# Test_Gate.net
KiCad netlist of a schematic drawn in Altium Designer
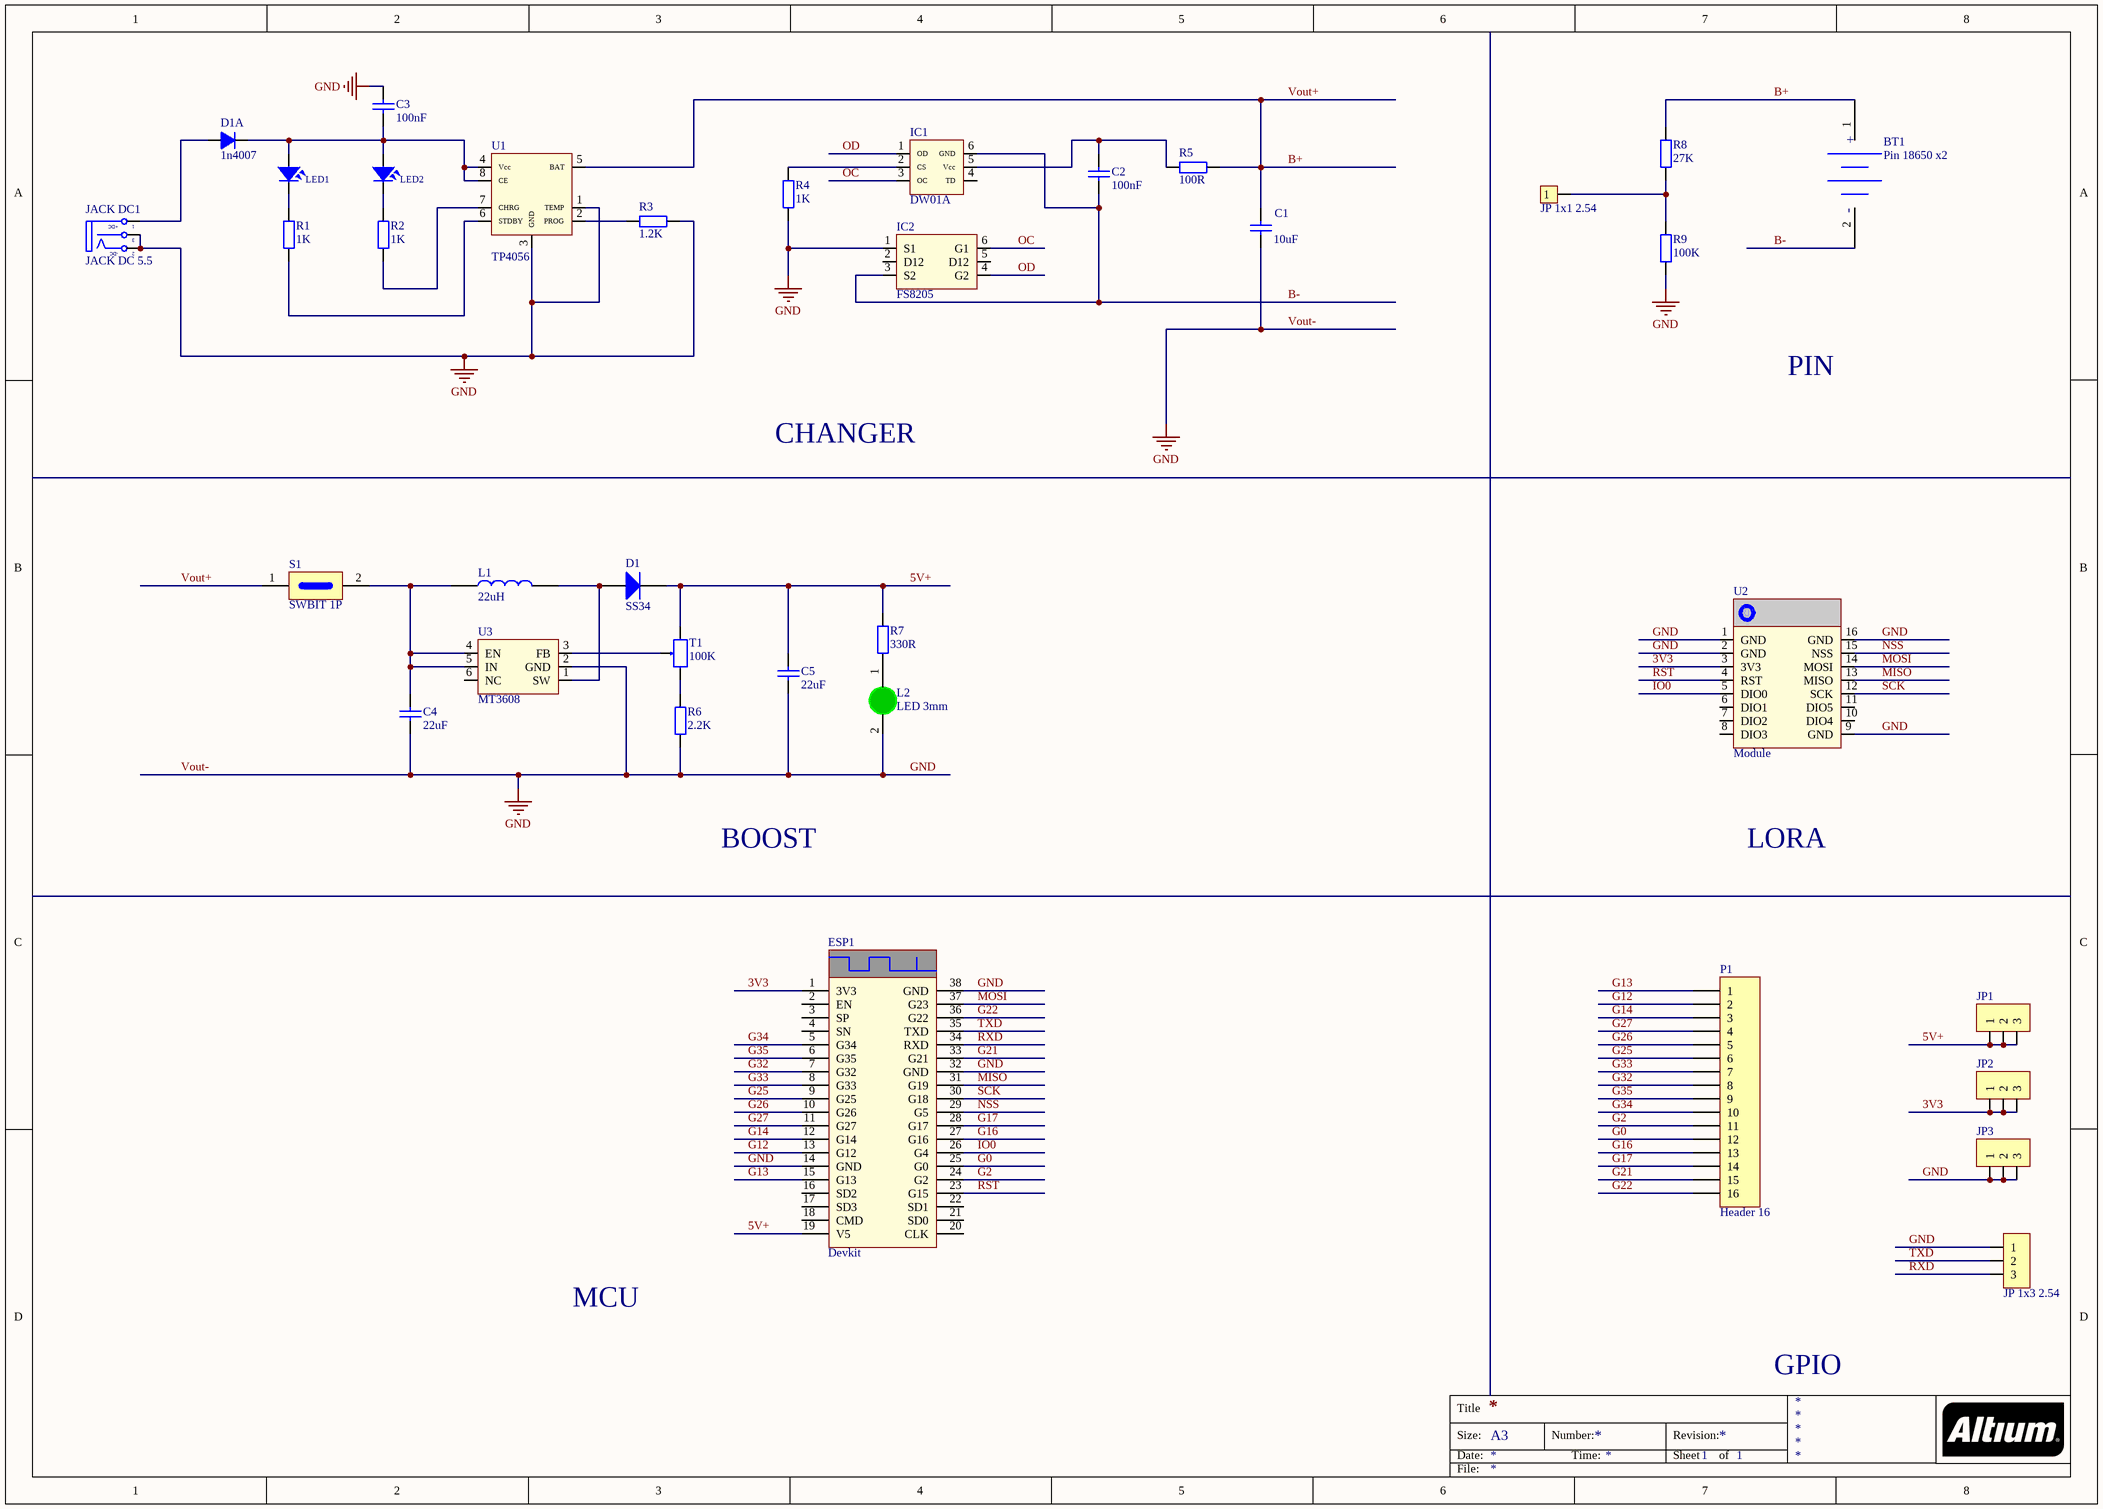
[diagram p0: Test Gate.SchDoc]

(export (version "E")
  (design (tool "Eeschema 10.0.6"))
  (components
    (comp (ref "BT1")
      (value "Pin 18650 x2")
      (footprint "De Pin 18650 x2")
      (libsource (lib "Lib_byDuy") (part "De Pin 18650 x2"))
    )
    (comp (ref "C1")
      (value "10uF")
      (footprint "tu 0805")
      (description "Dán")
      (libsource (lib "Altium_Lib_by_KhueNguyenCreator") (part "Tu 0805 104 50V 10%"))
    )
    (comp (ref "C2")
      (value "100nF")
      (footprint "tu 0805")
      (description "Dán")
      (libsource (lib "Altium_Lib_by_KhueNguyenCreator") (part "Tu 0805 104 50V 10%"))
    )
    (comp (ref "C3")
      (value "100nF")
      (footprint "tu 0805")
      (description "Dán")
      (libsource (lib "Altium_Lib_by_KhueNguyenCreator") (part "Tu 0805 104 50V 10%"))
    )
    (comp (ref "C4")
      (value "22uF")
      (footprint "tu 1206")
      (description "Dán")
      (libsource (lib "Altium_Lib_by_KhueNguyenCreator") (part "Tu 1206 226 16V 20%"))
    )
    (comp (ref "C5")
      (value "22uF")
      (footprint "tu 1206")
      (description "Dán")
      (libsource (lib "Altium_Lib_by_KhueNguyenCreator") (part "Tu 1206 226 16V 20%"))
    )
    (comp (ref "D1")
      (value "SS34")
      (footprint "DIODE SMA")
      (description "Dán")
      (libsource (lib "Altium_Lib_by_KhueNguyenCreator") (part "Diode SS34 ( 1N5822 )"))
    )
    (comp (ref "D1A")
      (value "1n4007")
      (footprint "DIODE 1A")
      (description "Cắm")
      (libsource (lib "Altium_Lib_by_KhueNguyenCreator") (part "Diode 1N4007"))
    )
    (comp (ref "ESP1")
      (value "Devkit")
      (footprint "ESP32 DEVKIT 38Pin")
      (description "Board")
      (libsource (lib "Lib_byDuy") (part "ESP32 DEV KIT"))
    )
    (comp (ref "IC1") (value "DW01A") (footprint "DW01A") (libsource (lib "Lib_byDuy") (part "DW01A")))
    (comp (ref "IC2")
      (value "FS8205")
      (footprint "FS8205")
      (description "SOT23-6")
      (libsource (lib "Lib_byDuy") (part "FS8205"))
    )
    (comp (ref "JACK DC1")
      (value "JACK DC 5.5")
      (footprint "JACK DC 5.5")
      (libsource (lib "Altium_Lib_by_KhueNguyenCreator") (part "JACK DC 5.5"))
    )
    (comp (ref "JP1")
      (value "JP 1x3 2.54")
      (footprint "JP 1x3 CT")
      (description "Cắm")
      (libsource (lib "Altium_Lib_by_KhueNguyenCreator") (part "JP 1x3 2.54 Cai Thang"))
    )
    (comp (ref "JP2")
      (value "JP 1x3 2.54")
      (footprint "JP 1x3 CT")
      (description "Cắm")
      (libsource (lib "Altium_Lib_by_KhueNguyenCreator") (part "JP 1x3 2.54 Cai Thang"))
    )
    (comp (ref "JP3")
      (value "JP 1x3 2.54")
      (footprint "JP 1x3 CT")
      (description "Cắm")
      (libsource (lib "Altium_Lib_by_KhueNguyenCreator") (part "JP 1x3 2.54 Cai Thang"))
    )
    (comp (ref "JP4")
      (value "JP 1x1 2.54")
      (footprint "JP 1x1 DT")
      (description "Cắm")
      (libsource (lib "Altium_Lib_by_KhueNguyenCreator") (part "JP 1x1 2.54 Duc Thang"))
    )
    (comp (ref "JP5")
      (value "JP 1x3 2.54")
      (footprint "JP 1x3 CT")
      (description "Cắm")
      (libsource (lib "") (part "JP 1x3 2.54 Cai Thang_1"))
    )
    (comp (ref "L1")
      (value "22uH")
      (footprint "Cuon Cam 7x7x5")
      (description "Dán")
      (libsource (lib "Altium_Lib_by_KhueNguyenCreator") (part "CUON CAM 47uH SMD"))
    )
    (comp (ref "L2")
      (value "LED 3mm")
      (footprint "LED-3MM-GREEN")
      (description "Cắm")
      (libsource (lib "Altium_Lib_by_KhueNguyenCreator") (part "LED 3mm Xanh La"))
    )
    (comp (ref "LED1")
      (value "LED SMD")
      (footprint "SM-LED-0805-Red")
      (libsource (lib "My library altium") (part "LED SMD 0805"))
    )
    (comp (ref "LED2")
      (value "LED SMD")
      (footprint "SM-LED-0805-Red")
      (libsource (lib "My library altium") (part "LED SMD 0805"))
    )
    (comp (ref "P1")
      (value "Header 16")
      (footprint "HDR1X16")
      (description "Header, 16-Pin")
      (fields (field (name "PUBLISHER") "Altium Limited"))
      (libsource (lib "My library altium") (part "Header 16"))
    )
    (comp (ref "R1")
      (value "1K")
      (footprint "tro smd 0805")
      (description "Dán")
      (libsource (lib "Altium_Lib_by_KhueNguyenCreator") (part "Tro 0805 5% 1k"))
    )
    (comp (ref "R2")
      (value "1K")
      (footprint "tro smd 0805")
      (description "Dán")
      (libsource (lib "Altium_Lib_by_KhueNguyenCreator") (part "Tro 0805 5% 1k"))
    )
    (comp (ref "R3")
      (value "1.2K")
      (footprint "tro smd 0805")
      (description "Dán")
      (libsource (lib "Altium_Lib_by_KhueNguyenCreator") (part "Tro 0805 5% 1k"))
    )
    (comp (ref "R4")
      (value "1K")
      (footprint "tro smd 0805")
      (description "Dán")
      (libsource (lib "Altium_Lib_by_KhueNguyenCreator") (part "Tro 0805 5% 1k"))
    )
    (comp (ref "R5")
      (value "100R")
      (footprint "tro smd 0805")
      (description "Dán")
      (libsource (lib "Altium_Lib_by_KhueNguyenCreator") (part "Tro 0805 5% 1k"))
    )
    (comp (ref "R6")
      (value "2.2K")
      (footprint "tro smd 0805")
      (description "Dán")
      (libsource (lib "Altium_Lib_by_KhueNguyenCreator") (part "Tro 0805 5% 1k"))
    )
    (comp (ref "R7")
      (value "330R")
      (footprint "tro smd 0805")
      (description "Dán")
      (libsource (lib "Altium_Lib_by_KhueNguyenCreator") (part "Tro 0805 5% 1k"))
    )
    (comp (ref "R8")
      (value "27K")
      (footprint "tro smd 0805")
      (description "Dán")
      (libsource (lib "Altium_Lib_by_KhueNguyenCreator") (part "Tro 0805 5% 1k"))
    )
    (comp (ref "R9")
      (value "100K")
      (footprint "tro smd 0805")
      (description "Dán")
      (libsource (lib "Altium_Lib_by_KhueNguyenCreator") (part "Tro 0805 5% 1k"))
    )
    (comp (ref "S1")
      (value "SWBIT 1P")
      (footprint "SWBIT 1P DIP")
      (libsource (lib "ThinhNguyenLib") (part "SWBIT 1P"))
    )
    (comp (ref "T1")
      (value "100K")
      (footprint "Bien Tro Vi Chinh Dung")
      (description "Cắm")
      (libsource (lib "Altium_Lib_by_KhueNguyenCreator") (part "Bien Tro Tinh Chinh 10K Dung"))
    )
    (comp (ref "U1") (value "TP4056") (footprint "TP4056") (libsource (lib "Lib_byDuy") (part "TP4056")))
    (comp (ref "U2")
      (value "Module")
      (footprint "LoRa Ra 02 Module 2")
      (libsource (lib "Lib_byDuy") (part "LoRa Ra 02 Module 2"))
    )
    (comp (ref "U3")
      (value "MT3608")
      (footprint "MT3608")
      (description "SMD")
      (libsource (lib "Lib_byDuy") (part "MT3608"))
    )
  )
  (nets
    (net (code "1") (name "/3V3") (class "Default")
      (node (ref "ESP1") (pin "1") (pinfunction "3V3_1") (pintype "passive"))
      (node (ref "JP2") (pin "1") (pinfunction "1_1") (pintype "passive"))
      (node (ref "JP2") (pin "2") (pinfunction "2_2") (pintype "passive"))
      (node (ref "JP2") (pin "3") (pinfunction "3_3") (pintype "passive"))
      (node (ref "U2") (pin "3") (pinfunction "3V3_3") (pintype "passive"))
    )
    (net (code "2") (name "/5V+") (class "Default")
      (node (ref "C5") (pin "1") (pinfunction "1_1") (pintype "passive"))
      (node (ref "D1") (pin "2") (pinfunction "K_2") (pintype "passive"))
      (node (ref "ESP1") (pin "19") (pinfunction "V5_19") (pintype "passive"))
      (node (ref "JP1") (pin "1") (pinfunction "1_1") (pintype "passive"))
      (node (ref "JP1") (pin "2") (pinfunction "2_2") (pintype "passive"))
      (node (ref "JP1") (pin "3") (pinfunction "3_3") (pintype "passive"))
      (node (ref "R7") (pin "1") (pinfunction "1_1") (pintype "passive"))
      (node (ref "T1") (pin "3") (pinfunction "3_3") (pintype "passive"))
    )
    (net (code "3") (name "/B+") (class "Default")
      (node (ref "BT1") (pin "1") (pinfunction "+_1") (pintype "passive"))
      (node (ref "C1") (pin "1") (pinfunction "1_1") (pintype "passive"))
      (node (ref "R5") (pin "2") (pinfunction "2_2") (pintype "passive"))
      (node (ref "R8") (pin "1") (pinfunction "1_1") (pintype "passive"))
      (node (ref "S1") (pin "1") (pinfunction "1_1") (pintype "passive"))
      (node (ref "U1") (pin "5") (pinfunction "BAT_5") (pintype "passive"))
    )
    (net (code "4") (name "/B-") (class "Default")
      (node (ref "BT1") (pin "2") (pinfunction "-_2") (pintype "passive"))
      (node (ref "C2") (pin "2") (pinfunction "2_2") (pintype "passive"))
      (node (ref "IC1") (pin "6") (pinfunction "GND_6") (pintype "passive"))
      (node (ref "IC2") (pin "3") (pinfunction "S2_3") (pintype "passive"))
    )
    (net (code "5") (name "/G0") (class "Default")
      (node (ref "ESP1") (pin "25") (pinfunction "G0_25") (pintype "passive"))
      (node (ref "P1") (pin "12") (pinfunction "12_12") (pintype "passive"))
    )
    (net (code "6") (name "/G2") (class "Default")
      (node (ref "ESP1") (pin "24") (pinfunction "G2_24") (pintype "passive"))
      (node (ref "P1") (pin "11") (pinfunction "11_11") (pintype "passive"))
    )
    (net (code "7") (name "/G12") (class "Default")
      (node (ref "ESP1") (pin "13") (pinfunction "G12_13") (pintype "passive"))
      (node (ref "P1") (pin "2") (pinfunction "2_2") (pintype "passive"))
    )
    (net (code "8") (name "/G13") (class "Default")
      (node (ref "ESP1") (pin "15") (pinfunction "G13_15") (pintype "passive"))
      (node (ref "P1") (pin "1") (pinfunction "1_1") (pintype "passive"))
    )
    (net (code "9") (name "/G14") (class "Default")
      (node (ref "ESP1") (pin "12") (pinfunction "G14_12") (pintype "passive"))
      (node (ref "P1") (pin "3") (pinfunction "3_3") (pintype "passive"))
    )
    (net (code "10") (name "/G16") (class "Default")
      (node (ref "ESP1") (pin "27") (pinfunction "G16_27") (pintype "passive"))
      (node (ref "P1") (pin "13") (pinfunction "13_13") (pintype "passive"))
    )
    (net (code "11") (name "/G17") (class "Default")
      (node (ref "ESP1") (pin "28") (pinfunction "G17_28") (pintype "passive"))
      (node (ref "P1") (pin "14") (pinfunction "14_14") (pintype "passive"))
    )
    (net (code "12") (name "/G21") (class "Default")
      (node (ref "ESP1") (pin "33") (pinfunction "G21_33") (pintype "passive"))
      (node (ref "P1") (pin "15") (pinfunction "15_15") (pintype "passive"))
    )
    (net (code "13") (name "/G22") (class "Default")
      (node (ref "ESP1") (pin "36") (pinfunction "G22_36") (pintype "passive"))
      (node (ref "P1") (pin "16") (pinfunction "16_16") (pintype "passive"))
    )
    (net (code "14") (name "/G25") (class "Default")
      (node (ref "ESP1") (pin "9") (pinfunction "G25_9") (pintype "passive"))
      (node (ref "P1") (pin "6") (pinfunction "6_6") (pintype "passive"))
    )
    (net (code "15") (name "/G26") (class "Default")
      (node (ref "ESP1") (pin "10") (pinfunction "G26_10") (pintype "passive"))
      (node (ref "P1") (pin "5") (pinfunction "5_5") (pintype "passive"))
    )
    (net (code "16") (name "/G27") (class "Default")
      (node (ref "ESP1") (pin "11") (pinfunction "G27_11") (pintype "passive"))
      (node (ref "P1") (pin "4") (pinfunction "4_4") (pintype "passive"))
    )
    (net (code "17") (name "/G32") (class "Default")
      (node (ref "ESP1") (pin "7") (pinfunction "G32_7") (pintype "passive"))
      (node (ref "P1") (pin "8") (pinfunction "8_8") (pintype "passive"))
    )
    (net (code "18") (name "/G33") (class "Default")
      (node (ref "ESP1") (pin "8") (pinfunction "G33_8") (pintype "passive"))
      (node (ref "P1") (pin "7") (pinfunction "7_7") (pintype "passive"))
    )
    (net (code "19") (name "/G34") (class "Default")
      (node (ref "ESP1") (pin "5") (pinfunction "G34_5") (pintype "passive"))
      (node (ref "P1") (pin "10") (pinfunction "10_10") (pintype "passive"))
    )
    (net (code "20") (name "/G35") (class "Default")
      (node (ref "ESP1") (pin "6") (pinfunction "G35_6") (pintype "passive"))
      (node (ref "P1") (pin "9") (pinfunction "9_9") (pintype "passive"))
    )
    (net (code "21") (name "/IO0") (class "Default")
      (node (ref "ESP1") (pin "26") (pinfunction "G4_26") (pintype "passive"))
      (node (ref "U2") (pin "5") (pinfunction "DIO0_5") (pintype "passive"))
    )
    (net (code "22") (name "/MISO") (class "Default")
      (node (ref "ESP1") (pin "31") (pinfunction "G19_31") (pintype "passive"))
      (node (ref "U2") (pin "13") (pinfunction "MISO_13") (pintype "passive"))
    )
    (net (code "23") (name "/MOSI") (class "Default")
      (node (ref "ESP1") (pin "37") (pinfunction "G23_37") (pintype "passive"))
      (node (ref "U2") (pin "14") (pinfunction "MOSI_14") (pintype "passive"))
    )
    (net (code "24") (name "/NSS") (class "Default")
      (node (ref "ESP1") (pin "29") (pinfunction "G5_29") (pintype "passive"))
      (node (ref "U2") (pin "15") (pinfunction "NSS_15") (pintype "passive"))
    )
    (net (code "25") (name "/OC") (class "Default")
      (node (ref "IC1") (pin "3") (pinfunction "OC_3") (pintype "passive"))
      (node (ref "IC2") (pin "6") (pinfunction "G1_6") (pintype "passive"))
    )
    (net (code "26") (name "/OD") (class "Default")
      (node (ref "IC1") (pin "1") (pinfunction "OD_1") (pintype "passive"))
      (node (ref "IC2") (pin "4") (pinfunction "G2_4") (pintype "passive"))
    )
    (net (code "27") (name "/RST") (class "Default")
      (node (ref "ESP1") (pin "23") (pinfunction "G15_23") (pintype "passive"))
      (node (ref "U2") (pin "4") (pinfunction "RST_4") (pintype "passive"))
    )
    (net (code "28") (name "/RXD") (class "Default")
      (node (ref "ESP1") (pin "34") (pinfunction "RXD_34") (pintype "passive"))
      (node (ref "JP5") (pin "3") (pinfunction "3_3") (pintype "passive"))
    )
    (net (code "29") (name "/SCK") (class "Default")
      (node (ref "ESP1") (pin "30") (pinfunction "G18_30") (pintype "passive"))
      (node (ref "U2") (pin "12") (pinfunction "SCK_12") (pintype "passive"))
    )
    (net (code "30") (name "/TXD") (class "Default")
      (node (ref "ESP1") (pin "35") (pinfunction "TXD_35") (pintype "passive"))
      (node (ref "JP5") (pin "2") (pinfunction "2_2") (pintype "passive"))
    )
    (net (code "31") (name "GND") (class "Default")
      (node (ref "C1") (pin "2") (pinfunction "2_2") (pintype "passive"))
      (node (ref "C3") (pin "1") (pinfunction "1_1") (pintype "passive"))
      (node (ref "C4") (pin "2") (pinfunction "2_2") (pintype "passive"))
      (node (ref "C5") (pin "2") (pinfunction "2_2") (pintype "passive"))
      (node (ref "ESP1") (pin "14") (pinfunction "GND_14") (pintype "passive"))
      (node (ref "ESP1") (pin "32") (pinfunction "GND_32") (pintype "passive"))
      (node (ref "ESP1") (pin "38") (pinfunction "GND_38") (pintype "passive"))
      (node (ref "IC2") (pin "1") (pinfunction "S1_1") (pintype "passive"))
      (node (ref "JACK DC1") (pin "2") (pinfunction "TN_2") (pintype "passive"))
      (node (ref "JACK DC1") (pin "3") (pinfunction "S_3") (pintype "power_in"))
      (node (ref "JP3") (pin "1") (pinfunction "1_1") (pintype "passive"))
      (node (ref "JP3") (pin "2") (pinfunction "2_2") (pintype "passive"))
      (node (ref "JP3") (pin "3") (pinfunction "3_3") (pintype "passive"))
      (node (ref "JP5") (pin "1") (pinfunction "1_1") (pintype "passive"))
      (node (ref "L2") (pin "2") (pinfunction "K_2") (pintype "passive"))
      (node (ref "R3") (pin "2") (pinfunction "2_2") (pintype "passive"))
      (node (ref "R4") (pin "2") (pinfunction "2_2") (pintype "passive"))
      (node (ref "R6") (pin "2") (pinfunction "2_2") (pintype "passive"))
      (node (ref "R9") (pin "2") (pinfunction "2_2") (pintype "passive"))
      (node (ref "U1") (pin "1") (pinfunction "TEMP_1") (pintype "passive"))
      (node (ref "U1") (pin "3") (pinfunction "GND_3") (pintype "passive"))
      (node (ref "U2") (pin "1") (pinfunction "GND_1") (pintype "passive"))
      (node (ref "U2") (pin "16") (pinfunction "GND_16") (pintype "passive"))
      (node (ref "U2") (pin "2") (pinfunction "GND_2") (pintype "passive"))
      (node (ref "U2") (pin "9") (pinfunction "GND_9") (pintype "passive"))
      (node (ref "U3") (pin "2") (pinfunction "GND_2") (pintype "passive"))
    )
    (net (code "32") (name "Net-(D1-A)") (class "Default")
      (node (ref "D1") (pin "1") (pinfunction "A_1") (pintype "passive"))
      (node (ref "L1") (pin "2") (pinfunction "2_2") (pintype "passive"))
      (node (ref "U3") (pin "1") (pinfunction "SW_1") (pintype "passive"))
    )
    (net (code "33") (name "Net-(D1A-A)") (class "Default")
      (node (ref "D1A") (pin "1") (pinfunction "A_1") (pintype "passive"))
      (node (ref "JACK DC1") (pin "1") (pinfunction "T_1") (pintype "passive"))
    )
    (net (code "34") (name "Net-(D1A-K)") (class "Default")
      (node (ref "C3") (pin "2") (pinfunction "2_2") (pintype "passive"))
      (node (ref "D1A") (pin "2") (pinfunction "K_2") (pintype "passive"))
      (node (ref "LED1") (pin "1") (pinfunction "1_1") (pintype "passive"))
      (node (ref "LED2") (pin "1") (pinfunction "1_1") (pintype "passive"))
      (node (ref "U1") (pin "4") (pinfunction "Vcc_4") (pintype "passive"))
      (node (ref "U1") (pin "8") (pinfunction "CE_8") (pintype "passive"))
    )
    (net (code "35") (name "Net-(IC1-CS)") (class "Default")
      (node (ref "IC1") (pin "2") (pinfunction "CS_2") (pintype "passive"))
      (node (ref "R4") (pin "1") (pinfunction "1_1") (pintype "passive"))
    )
    (net (code "36") (name "Net-(IC1-Vcc)") (class "Default")
      (node (ref "C2") (pin "1") (pinfunction "1_1") (pintype "passive"))
      (node (ref "IC1") (pin "5") (pinfunction "Vcc_5") (pintype "passive"))
      (node (ref "R5") (pin "1") (pinfunction "1_1") (pintype "passive"))
    )
    (net (code "37") (name "Net-(JP4-Pad1)") (class "Default")
      (node (ref "JP4") (pin "1") (pinfunction "1_1") (pintype "passive"))
      (node (ref "R8") (pin "2") (pinfunction "2_2") (pintype "passive"))
      (node (ref "R9") (pin "1") (pinfunction "1_1") (pintype "passive"))
    )
    (net (code "38") (name "Net-(L2-A)") (class "Default")
      (node (ref "L2") (pin "1") (pinfunction "A_1") (pintype "passive"))
      (node (ref "R7") (pin "2") (pinfunction "2_2") (pintype "passive"))
    )
    (net (code "39") (name "Net-(LED1-Pad2)") (class "Default")
      (node (ref "LED1") (pin "2") (pinfunction "2_2") (pintype "passive"))
      (node (ref "R1") (pin "1") (pinfunction "1_1") (pintype "passive"))
    )
    (net (code "40") (name "Net-(LED2-Pad2)") (class "Default")
      (node (ref "LED2") (pin "2") (pinfunction "2_2") (pintype "passive"))
      (node (ref "R2") (pin "1") (pinfunction "1_1") (pintype "passive"))
    )
    (net (code "41") (name "Net-(R6-Pad1)") (class "Default")
      (node (ref "R6") (pin "1") (pinfunction "1_1") (pintype "passive"))
      (node (ref "T1") (pin "1") (pinfunction "1_1") (pintype "passive"))
    )
    (net (code "42") (name "Net-(U1-CHRG)") (class "Default")
      (node (ref "R2") (pin "2") (pinfunction "2_2") (pintype "passive"))
      (node (ref "U1") (pin "7") (pinfunction "CHRG_7") (pintype "passive"))
    )
    (net (code "43") (name "Net-(U1-PROG)") (class "Default")
      (node (ref "R3") (pin "1") (pinfunction "1_1") (pintype "passive"))
      (node (ref "U1") (pin "2") (pinfunction "PROG_2") (pintype "passive"))
    )
    (net (code "44") (name "Net-(U1-STDBY)") (class "Default")
      (node (ref "R1") (pin "2") (pinfunction "2_2") (pintype "passive"))
      (node (ref "U1") (pin "6") (pinfunction "STDBY_6") (pintype "passive"))
    )
    (net (code "45") (name "Net-(U3-EN)") (class "Default")
      (node (ref "C4") (pin "1") (pinfunction "1_1") (pintype "passive"))
      (node (ref "L1") (pin "1") (pinfunction "1_1") (pintype "passive"))
      (node (ref "S1") (pin "2") (pinfunction "2_2") (pintype "passive"))
      (node (ref "U3") (pin "4") (pinfunction "EN_4") (pintype "passive"))
      (node (ref "U3") (pin "5") (pinfunction "IN_5") (pintype "passive"))
    )
    (net (code "46") (name "Net-(U3-FB)") (class "Default")
      (node (ref "T1") (pin "2") (pinfunction "2_2") (pintype "passive"))
      (node (ref "U3") (pin "3") (pinfunction "FB_3") (pintype "passive"))
    )
    (net (code "47") (name "unconnected-(ESP1-CLK-Pad20)") (class "Default")
      (node (ref "ESP1") (pin "20") (pinfunction "CLK_20") (pintype "passive"))
    )
    (net (code "48") (name "unconnected-(ESP1-CMD-Pad18)") (class "Default")
      (node (ref "ESP1") (pin "18") (pinfunction "CMD_18") (pintype "passive"))
    )
    (net (code "49") (name "unconnected-(ESP1-EN-Pad2)") (class "Default")
      (node (ref "ESP1") (pin "2") (pinfunction "EN_2") (pintype "passive"))
    )
    (net (code "50") (name "unconnected-(ESP1-SD0-Pad21)") (class "Default")
      (node (ref "ESP1") (pin "21") (pinfunction "SD0_21") (pintype "passive"))
    )
    (net (code "51") (name "unconnected-(ESP1-SD1-Pad22)") (class "Default")
      (node (ref "ESP1") (pin "22") (pinfunction "SD1_22") (pintype "passive"))
    )
    (net (code "52") (name "unconnected-(ESP1-SD2-Pad16)") (class "Default")
      (node (ref "ESP1") (pin "16") (pinfunction "SD2_16") (pintype "passive"))
    )
    (net (code "53") (name "unconnected-(ESP1-SD3-Pad17)") (class "Default")
      (node (ref "ESP1") (pin "17") (pinfunction "SD3_17") (pintype "passive"))
    )
    (net (code "54") (name "unconnected-(ESP1-SN-Pad4)") (class "Default")
      (node (ref "ESP1") (pin "4") (pinfunction "SN_4") (pintype "passive"))
    )
    (net (code "55") (name "unconnected-(ESP1-SP-Pad3)") (class "Default")
      (node (ref "ESP1") (pin "3") (pinfunction "SP_3") (pintype "passive"))
    )
    (net (code "56") (name "unconnected-(IC1-TD-Pad4)") (class "Default")
      (node (ref "IC1") (pin "4") (pinfunction "TD_4") (pintype "passive"))
    )
    (net (code "57") (name "unconnected-(IC2-D12-Pad2)") (class "Default")
      (node (ref "IC2") (pin "2") (pinfunction "D12_2") (pintype "passive"))
    )
    (net (code "58") (name "unconnected-(IC2-D12-Pad5)") (class "Default")
      (node (ref "IC2") (pin "5") (pinfunction "D12_5") (pintype "passive"))
    )
    (net (code "59") (name "unconnected-(U2-DIO1-Pad6)") (class "Default")
      (node (ref "U2") (pin "6") (pinfunction "DIO1_6") (pintype "passive"))
    )
    (net (code "60") (name "unconnected-(U2-DIO2-Pad7)") (class "Default")
      (node (ref "U2") (pin "7") (pinfunction "DIO2_7") (pintype "passive"))
    )
    (net (code "61") (name "unconnected-(U2-DIO3-Pad8)") (class "Default")
      (node (ref "U2") (pin "8") (pinfunction "DIO3_8") (pintype "passive"))
    )
    (net (code "62") (name "unconnected-(U2-DIO4-Pad10)") (class "Default")
      (node (ref "U2") (pin "10") (pinfunction "DIO4_10") (pintype "passive"))
    )
    (net (code "63") (name "unconnected-(U2-DIO5-Pad11)") (class "Default")
      (node (ref "U2") (pin "11") (pinfunction "DIO5_11") (pintype "passive"))
    )
    (net (code "64") (name "unconnected-(U3-NC-Pad6)") (class "Default")
      (node (ref "U3") (pin "6") (pinfunction "NC_6") (pintype "passive"))
    )
  )
)
